# ProPrj_BLDC_complete_drive_controller_RE.net
KiCad netlist of a schematic drawn in EasyEDA Pro
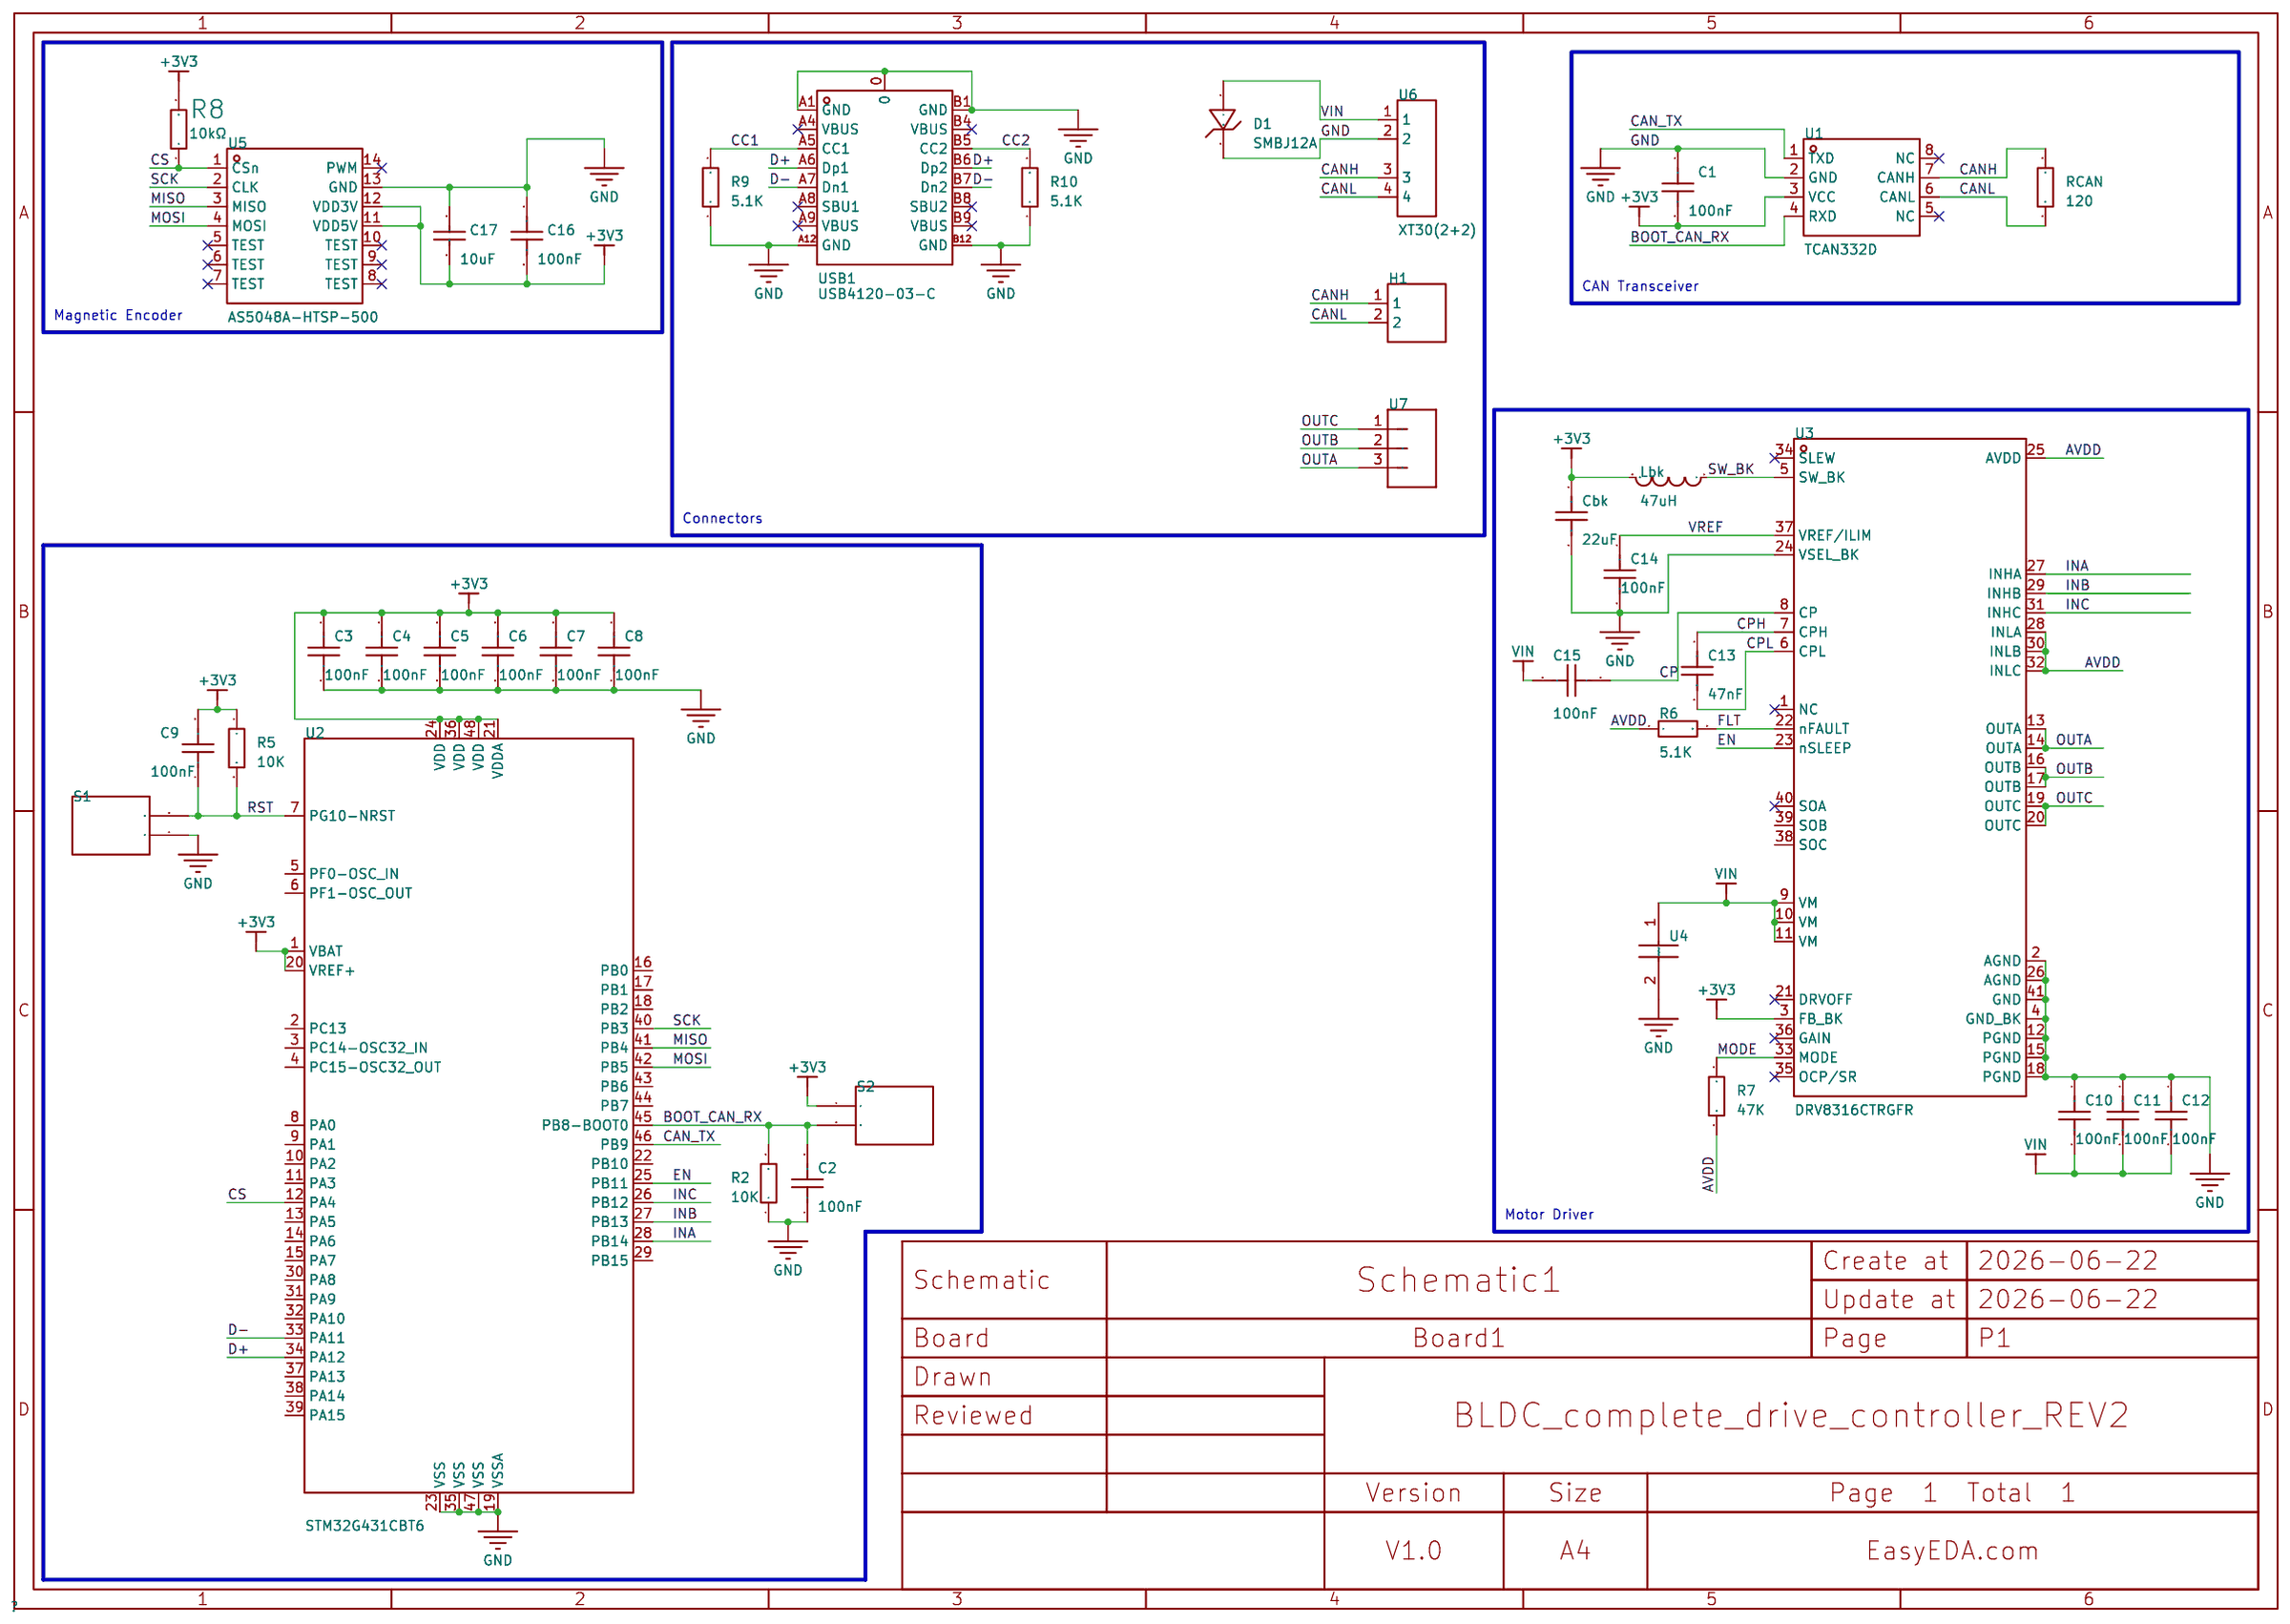
[diagram p0: schematic sheet]

(export (version "E")
  (design (tool "Eeschema 10.0.6"))
  (components
    (comp (ref "C1")
      (value "100nF")
      (footprint "easyedapro:C0603")
      (libsource (lib "easyedapro") (part "CAP"))
    )
    (comp (ref "C2")
      (value "100nF")
      (footprint "easyedapro:C0603")
      (libsource (lib "easyedapro") (part "CAP"))
    )
    (comp (ref "C3")
      (value "100nF")
      (footprint "easyedapro:C0603")
      (libsource (lib "easyedapro") (part "CAP"))
    )
    (comp (ref "C4")
      (value "100nF")
      (footprint "easyedapro:C0603")
      (libsource (lib "easyedapro") (part "CAP"))
    )
    (comp (ref "C5")
      (value "100nF")
      (footprint "easyedapro:C0603")
      (libsource (lib "easyedapro") (part "CAP"))
    )
    (comp (ref "C6")
      (value "100nF")
      (footprint "easyedapro:C0603")
      (libsource (lib "easyedapro") (part "CAP"))
    )
    (comp (ref "C7")
      (value "100nF")
      (footprint "easyedapro:C0603")
      (libsource (lib "easyedapro") (part "CAP"))
    )
    (comp (ref "C8")
      (value "100nF")
      (footprint "easyedapro:C0603")
      (libsource (lib "easyedapro") (part "CAP"))
    )
    (comp (ref "C9")
      (value "100nF")
      (footprint "easyedapro:C0603")
      (libsource (lib "easyedapro") (part "CAP"))
    )
    (comp (ref "C10")
      (value "100nF")
      (footprint "easyedapro:C0603")
      (libsource (lib "easyedapro") (part "CAP"))
    )
    (comp (ref "C11")
      (value "100nF")
      (footprint "easyedapro:C0603")
      (libsource (lib "easyedapro") (part "CAP"))
    )
    (comp (ref "C12")
      (value "100nF")
      (footprint "easyedapro:C0603")
      (libsource (lib "easyedapro") (part "CAP"))
    )
    (comp (ref "C13")
      (value "47nF")
      (footprint "easyedapro:C0603")
      (libsource (lib "easyedapro") (part "CAP"))
    )
    (comp (ref "C14")
      (value "100nF")
      (footprint "easyedapro:C0603")
      (libsource (lib "easyedapro") (part "CAP"))
    )
    (comp (ref "C15")
      (value "100nF")
      (footprint "easyedapro:C0603")
      (libsource (lib "easyedapro") (part "CAP"))
    )
    (comp (ref "C16")
      (value "100nF")
      (footprint "easyedapro:C0603")
      (description "Capacitance:100nF Tolerance:±10% Tolerance:±10% Voltage Rating:50V Temperature Coefficient:X7R")
      (fields
        (field (name "Manufacturer Part") "CC0603KRX7R9BB104")
        (field (name "Manufacturer") "YAGEO(国巨)")
      )
      (libsource (lib "easyedapro") (part "CC0603KRX7R9BB104"))
    )
    (comp (ref "C17")
      (value "10uF")
      (footprint "easyedapro:C0402")
      (description "Capacitance:10uF Tolerance:±20% Tolerance:±20% Voltage Rating:6.3V Temperature Coefficient:X5R")
      (fields
        (field (name "Manufacturer Part") "CL05A106MQ5NUNC")
        (field (name "Manufacturer") "SAMSUNG(三星)")
      )
      (libsource (lib "easyedapro") (part "CL05A106MQ5NUNC"))
    )
    (comp (ref "Cbk")
      (value "22uF")
      (footprint "easyedapro:C0603")
      (libsource (lib "easyedapro") (part "CAP"))
    )
    (comp (ref "D1")
      (value "SMBJ12A")
      (footprint "easyedapro:SMB_L4.6-W3.6-LS5.3-RD")
      (libsource (lib "easyedapro") (part "SMBJ12A-C127552"))
    )
    (comp (ref "H1")
      (value "~")
      (footprint "easyedapro:HDR-TH_2P-P2.54-V-M-1")
      (libsource (lib "easyedapro") (part "210S-1*2P L=11.6MMGold-plated black"))
    )
    (comp (ref "Lbk")
      (value "47uH")
      (footprint "easyedapro:L0805")
      (libsource (lib "easyedapro") (part "电感"))
    )
    (comp (ref "R2") (value "10K") (footprint "easyedapro:R0402") (libsource (lib "easyedapro") (part "Res")))
    (comp (ref "R5") (value "10K") (footprint "easyedapro:R0402") (libsource (lib "easyedapro") (part "Res")))
    (comp (ref "R6")
      (value "5.1K")
      (footprint "easyedapro:R0402")
      (libsource (lib "easyedapro") (part "Res"))
    )
    (comp (ref "R7") (value "47K") (footprint "easyedapro:R0402") (libsource (lib "easyedapro") (part "Res")))
    (comp (ref "R8")
      (value "10kΩ")
      (footprint "easyedapro:R0603")
      (fields
        (field (name "Manufacturer Part") "0603WAF1002T5E")
        (field (name "Manufacturer") "UNI-ROYAL(厚声)")
        (field (name "Tolerance") "±1%")
      )
      (libsource (lib "easyedapro") (part "0603WAF1002T5E"))
    )
    (comp (ref "R9")
      (value "5.1K")
      (footprint "easyedapro:R0402")
      (libsource (lib "easyedapro") (part "Res"))
    )
    (comp (ref "R10")
      (value "5.1K")
      (footprint "easyedapro:R0402")
      (libsource (lib "easyedapro") (part "Res"))
    )
    (comp (ref "RCAN")
      (value "120")
      (footprint "easyedapro:R0402")
      (libsource (lib "easyedapro") (part "Res"))
    )
    (comp (ref "S1")
      (value "~")
      (footprint "easyedapro:95C04A3GWRT")
      (libsource (lib "easyedapro") (part "95c04a3gwrt"))
    )
    (comp (ref "S2")
      (value "~")
      (footprint "easyedapro:95C04A3GWRT")
      (libsource (lib "easyedapro") (part "95c04a3gwrt"))
    )
    (comp (ref "U1")
      (value "TCAN332D")
      (footprint "easyedapro:SOIC-8_L4.9-W3.9-P1.27-LS6.0-BL")
      (fields (field (name "Manufacturer") "TI(德州仪器)"))
      (libsource (lib "easyedapro") (part "TCAN332D"))
    )
    (comp (ref "U2")
      (value "STM32G431CBT6")
      (footprint "easyedapro:LQFP-48_L7.0-W7.0-P0.50-LS9.0-BL")
      (fields (field (name "Manufacturer") "ST(意法半导体)"))
      (libsource (lib "easyedapro") (part "STM32G431CBT6"))
    )
    (comp (ref "U3")
      (value "DRV8316CTRGFR")
      (footprint "easyedapro:VQFN-40_L7.0-W5.0-P0.50-TL-EP5.7")
      (fields (field (name "Manufacturer") "TI(德州仪器)"))
      (libsource (lib "easyedapro") (part "DRV8316CTRGFR"))
    )
    (comp (ref "U4")
      (value "aha0608470m035r")
      (footprint "easyedapro:CAPAE660X850N")
      (libsource (lib "easyedapro") (part "aha0608470m035r"))
    )
    (comp (ref "U5")
      (value "AS5048A-HTSP-500")
      (footprint "easyedapro:TSSOP-14_L5.0-W4.4-P0.65-LS6.4-BL")
      (fields (field (name "Manufacturer") "ams(艾迈斯半导体)"))
      (libsource (lib "easyedapro") (part "AS5048A-HTSP-500"))
    )
    (comp (ref "U6")
      (value "XT30(2+2)")
      (footprint "easyedapro:CONN-TH_XT30-2-2")
      (libsource (lib "easyedapro") (part "XT30(2+2)"))
    )
    (comp (ref "U7")
      (value "~")
      (footprint "easyedapro:SCREWTERMINAL-3.5MM-3")
      (libsource (lib "easyedapro") (part "CONN_03_SCREW"))
    )
    (comp (ref "USB1")
      (value "USB4120-03-C")
      (footprint "easyedapro:TYPE-C-SMD_USB4120-03-C")
      (fields (field (name "Manufacturer") "GCT"))
      (libsource (lib "easyedapro") (part "USB4120-03-C"))
    )
  )
  (nets
    (net (code "1") (name "+3V3") (class "Default")
      (node (ref "C1") (pin "2") (pinfunction "2_2") (pintype "input"))
      (node (ref "C16") (pin "2") (pinfunction "2_2") (pintype "unspecified"))
      (node (ref "C17") (pin "1") (pinfunction "1_1") (pintype "input"))
      (node (ref "C3") (pin "2") (pinfunction "2_2") (pintype "input"))
      (node (ref "C4") (pin "2") (pinfunction "2_2") (pintype "input"))
      (node (ref "C5") (pin "2") (pinfunction "2_2") (pintype "input"))
      (node (ref "C6") (pin "2") (pinfunction "2_2") (pintype "input"))
      (node (ref "C7") (pin "2") (pinfunction "2_2") (pintype "input"))
      (node (ref "C8") (pin "2") (pinfunction "2_2") (pintype "input"))
      (node (ref "C9") (pin "2") (pinfunction "2_2") (pintype "input"))
      (node (ref "Cbk") (pin "1") (pinfunction "1_1") (pintype "input"))
      (node (ref "Lbk") (pin "2") (pinfunction "2_2") (pintype "input"))
      (node (ref "R5") (pin "1") (pinfunction "1_1") (pintype "input"))
      (node (ref "R8") (pin "2") (pinfunction "2_2") (pintype "input"))
      (node (ref "S2") (pin "1") (pinfunction "1_1") (pintype "unspecified"))
      (node (ref "U1") (pin "3") (pinfunction "VCC_3") (pintype "input"))
      (node (ref "U2") (pin "1") (pinfunction "VBAT_1") (pintype "unspecified"))
      (node (ref "U2") (pin "20") (pinfunction "VREF+_20") (pintype "unspecified"))
      (node (ref "U2") (pin "21") (pinfunction "VDDA_21") (pintype "unspecified"))
      (node (ref "U2") (pin "24") (pinfunction "VDD_24") (pintype "unspecified"))
      (node (ref "U2") (pin "36") (pinfunction "VDD_36") (pintype "unspecified"))
      (node (ref "U2") (pin "48") (pinfunction "VDD_48") (pintype "unspecified"))
      (node (ref "U3") (pin "3") (pinfunction "FB_BK_3") (pintype "unspecified"))
      (node (ref "U5") (pin "11") (pinfunction "VDD5V_11") (pintype "unspecified"))
      (node (ref "U5") (pin "12") (pinfunction "VDD3V_12") (pintype "unspecified"))
    )
    (net (code "2") (name "/AVDD") (class "Default")
      (node (ref "R6") (pin "1") (pinfunction "1_1") (pintype "input"))
      (node (ref "R7") (pin "2") (pinfunction "2_2") (pintype "input"))
      (node (ref "U3") (pin "25") (pinfunction "AVDD_25") (pintype "unspecified"))
      (node (ref "U3") (pin "28") (pinfunction "INLA_28") (pintype "unspecified"))
      (node (ref "U3") (pin "30") (pinfunction "INLB_30") (pintype "unspecified"))
      (node (ref "U3") (pin "32") (pinfunction "INLC_32") (pintype "unspecified"))
    )
    (net (code "3") (name "/BOOT_CAN_RX") (class "Default")
      (node (ref "C2") (pin "2") (pinfunction "2_2") (pintype "input"))
      (node (ref "R2") (pin "2") (pinfunction "2_2") (pintype "input"))
      (node (ref "S2") (pin "2") (pinfunction "2_2") (pintype "unspecified"))
      (node (ref "U1") (pin "4") (pinfunction "RXD_4") (pintype "input"))
      (node (ref "U2") (pin "45") (pinfunction "PB8-BOOT0_45") (pintype "unspecified"))
    )
    (net (code "4") (name "/CANH") (class "Default")
      (node (ref "H1") (pin "1") (pinfunction "1_1") (pintype "unspecified"))
      (node (ref "RCAN") (pin "2") (pinfunction "2_2") (pintype "input"))
      (node (ref "U1") (pin "7") (pinfunction "CANH_7") (pintype "input"))
      (node (ref "U6") (pin "3") (pinfunction "3_3") (pintype "unspecified"))
    )
    (net (code "5") (name "/CANL") (class "Default")
      (node (ref "H1") (pin "2") (pinfunction "2_2") (pintype "unspecified"))
      (node (ref "RCAN") (pin "1") (pinfunction "1_1") (pintype "input"))
      (node (ref "U1") (pin "6") (pinfunction "CANL_6") (pintype "input"))
      (node (ref "U6") (pin "4") (pinfunction "4_4") (pintype "unspecified"))
    )
    (net (code "6") (name "/CAN_TX") (class "Default")
      (node (ref "U1") (pin "1") (pinfunction "TXD_1") (pintype "input"))
      (node (ref "U2") (pin "46") (pinfunction "PB9_46") (pintype "unspecified"))
    )
    (net (code "7") (name "/CC1") (class "Default")
      (node (ref "R9") (pin "2") (pinfunction "2_2") (pintype "input"))
      (node (ref "USB1") (pin "A5") (pinfunction "CC1_A5") (pintype "unspecified"))
    )
    (net (code "8") (name "/CC2") (class "Default")
      (node (ref "R10") (pin "2") (pinfunction "2_2") (pintype "input"))
      (node (ref "USB1") (pin "B5") (pinfunction "CC2_B5") (pintype "unspecified"))
    )
    (net (code "9") (name "/CP") (class "Default")
      (node (ref "C15") (pin "1") (pinfunction "1_1") (pintype "input"))
      (node (ref "U3") (pin "8") (pinfunction "CP_8") (pintype "unspecified"))
    )
    (net (code "10") (name "/CPH") (class "Default")
      (node (ref "C13") (pin "1") (pinfunction "1_1") (pintype "input"))
      (node (ref "U3") (pin "7") (pinfunction "CPH_7") (pintype "unspecified"))
    )
    (net (code "11") (name "/CPL") (class "Default")
      (node (ref "C13") (pin "2") (pinfunction "2_2") (pintype "input"))
      (node (ref "U3") (pin "6") (pinfunction "CPL_6") (pintype "unspecified"))
    )
    (net (code "12") (name "/CS") (class "Default")
      (node (ref "R8") (pin "1") (pinfunction "1_1") (pintype "input"))
      (node (ref "U2") (pin "12") (pinfunction "PA4_12") (pintype "unspecified"))
      (node (ref "U5") (pin "1") (pinfunction "CSn_1") (pintype "unspecified"))
    )
    (net (code "13") (name "/D+") (class "Default")
      (node (ref "U2") (pin "34") (pinfunction "PA12_34") (pintype "unspecified"))
      (node (ref "USB1") (pin "A6") (pinfunction "Dp1_A6") (pintype "unspecified"))
      (node (ref "USB1") (pin "B6") (pinfunction "Dp2_B6") (pintype "unspecified"))
    )
    (net (code "14") (name "/D-") (class "Default")
      (node (ref "U2") (pin "33") (pinfunction "PA11_33") (pintype "unspecified"))
      (node (ref "USB1") (pin "A7") (pinfunction "Dn1_A7") (pintype "unspecified"))
      (node (ref "USB1") (pin "B7") (pinfunction "Dn2_B7") (pintype "unspecified"))
    )
    (net (code "15") (name "/EN") (class "Default")
      (node (ref "U2") (pin "25") (pinfunction "PB11_25") (pintype "unspecified"))
      (node (ref "U3") (pin "23") (pinfunction "nSLEEP_23") (pintype "unspecified"))
    )
    (net (code "16") (name "/FLT") (class "Default")
      (node (ref "R6") (pin "2") (pinfunction "2_2") (pintype "input"))
      (node (ref "U3") (pin "22") (pinfunction "nFAULT_22") (pintype "unspecified"))
    )
    (net (code "17") (name "/INA") (class "Default")
      (node (ref "U2") (pin "28") (pinfunction "PB14_28") (pintype "unspecified"))
      (node (ref "U3") (pin "27") (pinfunction "INHA_27") (pintype "unspecified"))
    )
    (net (code "18") (name "/INB") (class "Default")
      (node (ref "U2") (pin "27") (pinfunction "PB13_27") (pintype "unspecified"))
      (node (ref "U3") (pin "29") (pinfunction "INHB_29") (pintype "unspecified"))
    )
    (net (code "19") (name "/INC") (class "Default")
      (node (ref "U2") (pin "26") (pinfunction "PB12_26") (pintype "unspecified"))
      (node (ref "U3") (pin "31") (pinfunction "INHC_31") (pintype "unspecified"))
    )
    (net (code "20") (name "/MISO") (class "Default")
      (node (ref "U2") (pin "41") (pinfunction "PB4_41") (pintype "unspecified"))
      (node (ref "U5") (pin "3") (pinfunction "MISO_3") (pintype "unspecified"))
    )
    (net (code "21") (name "/MODE") (class "Default")
      (node (ref "R7") (pin "1") (pinfunction "1_1") (pintype "input"))
      (node (ref "U3") (pin "33") (pinfunction "MODE_33") (pintype "unspecified"))
    )
    (net (code "22") (name "/MOSI") (class "Default")
      (node (ref "U2") (pin "42") (pinfunction "PB5_42") (pintype "unspecified"))
      (node (ref "U5") (pin "4") (pinfunction "MOSI_4") (pintype "unspecified"))
    )
    (net (code "23") (name "/OUTA") (class "Default")
      (node (ref "U3") (pin "13") (pinfunction "OUTA_13") (pintype "unspecified"))
      (node (ref "U3") (pin "14") (pinfunction "OUTA_14") (pintype "unspecified"))
      (node (ref "U7") (pin "3") (pinfunction "3_3") (pintype "unspecified"))
    )
    (net (code "24") (name "/OUTB") (class "Default")
      (node (ref "U3") (pin "16") (pinfunction "OUTB_16") (pintype "unspecified"))
      (node (ref "U3") (pin "17") (pinfunction "OUTB_17") (pintype "unspecified"))
      (node (ref "U7") (pin "2") (pinfunction "2_2") (pintype "unspecified"))
    )
    (net (code "25") (name "/OUTC") (class "Default")
      (node (ref "U3") (pin "19") (pinfunction "OUTC_19") (pintype "unspecified"))
      (node (ref "U3") (pin "20") (pinfunction "OUTC_20") (pintype "unspecified"))
      (node (ref "U7") (pin "1") (pinfunction "1_1") (pintype "unspecified"))
    )
    (net (code "26") (name "/RST") (class "Default")
      (node (ref "C9") (pin "1") (pinfunction "1_1") (pintype "input"))
      (node (ref "R5") (pin "2") (pinfunction "2_2") (pintype "input"))
      (node (ref "S1") (pin "2") (pinfunction "2_2") (pintype "unspecified"))
      (node (ref "U2") (pin "7") (pinfunction "PG10-NRST_7") (pintype "unspecified"))
    )
    (net (code "27") (name "/SCK") (class "Default")
      (node (ref "U2") (pin "40") (pinfunction "PB3_40") (pintype "unspecified"))
      (node (ref "U5") (pin "2") (pinfunction "CLK_2") (pintype "unspecified"))
    )
    (net (code "28") (name "/SW_BK") (class "Default")
      (node (ref "Lbk") (pin "1") (pinfunction "1_1") (pintype "input"))
      (node (ref "U3") (pin "5") (pinfunction "SW_BK_5") (pintype "unspecified"))
    )
    (net (code "29") (name "/VREF") (class "Default")
      (node (ref "C14") (pin "1") (pinfunction "1_1") (pintype "input"))
      (node (ref "U3") (pin "37") (pinfunction "VREF/ILIM_37") (pintype "unspecified"))
    )
    (net (code "30") (name "GND") (class "Default")
      (node (ref "C1") (pin "1") (pinfunction "1_1") (pintype "input"))
      (node (ref "C10") (pin "1") (pinfunction "1_1") (pintype "input"))
      (node (ref "C11") (pin "1") (pinfunction "1_1") (pintype "input"))
      (node (ref "C12") (pin "1") (pinfunction "1_1") (pintype "input"))
      (node (ref "C14") (pin "2") (pinfunction "2_2") (pintype "input"))
      (node (ref "C16") (pin "1") (pinfunction "1_1") (pintype "unspecified"))
      (node (ref "C17") (pin "2") (pinfunction "2_2") (pintype "input"))
      (node (ref "C2") (pin "1") (pinfunction "1_1") (pintype "input"))
      (node (ref "C3") (pin "1") (pinfunction "1_1") (pintype "input"))
      (node (ref "C4") (pin "1") (pinfunction "1_1") (pintype "input"))
      (node (ref "C5") (pin "1") (pinfunction "1_1") (pintype "input"))
      (node (ref "C6") (pin "1") (pinfunction "1_1") (pintype "input"))
      (node (ref "C7") (pin "1") (pinfunction "1_1") (pintype "input"))
      (node (ref "C8") (pin "1") (pinfunction "1_1") (pintype "input"))
      (node (ref "Cbk") (pin "2") (pinfunction "2_2") (pintype "input"))
      (node (ref "D1") (pin "1") (pinfunction "C_1") (pintype "unspecified"))
      (node (ref "R10") (pin "1") (pinfunction "1_1") (pintype "input"))
      (node (ref "R2") (pin "1") (pinfunction "1_1") (pintype "input"))
      (node (ref "R9") (pin "1") (pinfunction "1_1") (pintype "input"))
      (node (ref "S1") (pin "1") (pinfunction "1_1") (pintype "unspecified"))
      (node (ref "U1") (pin "2") (pinfunction "GND_2") (pintype "input"))
      (node (ref "U2") (pin "19") (pinfunction "VSSA_19") (pintype "unspecified"))
      (node (ref "U2") (pin "23") (pinfunction "VSS_23") (pintype "unspecified"))
      (node (ref "U2") (pin "35") (pinfunction "VSS_35") (pintype "unspecified"))
      (node (ref "U2") (pin "47") (pinfunction "VSS_47") (pintype "unspecified"))
      (node (ref "U3") (pin "12") (pinfunction "PGND_12") (pintype "unspecified"))
      (node (ref "U3") (pin "15") (pinfunction "PGND_15") (pintype "unspecified"))
      (node (ref "U3") (pin "18") (pinfunction "PGND_18") (pintype "unspecified"))
      (node (ref "U3") (pin "2") (pinfunction "AGND_2") (pintype "unspecified"))
      (node (ref "U3") (pin "24") (pinfunction "VSEL_BK_24") (pintype "unspecified"))
      (node (ref "U3") (pin "26") (pinfunction "AGND_26") (pintype "unspecified"))
      (node (ref "U3") (pin "4") (pinfunction "GND_BK_4") (pintype "unspecified"))
      (node (ref "U3") (pin "41") (pinfunction "GND_41") (pintype "unspecified"))
      (node (ref "U4") (pin "2") (pinfunction "~_2") (pintype "unspecified"))
      (node (ref "U5") (pin "13") (pinfunction "GND_13") (pintype "unspecified"))
      (node (ref "U6") (pin "2") (pinfunction "2_2") (pintype "unspecified"))
      (node (ref "USB1") (pin "0") (pinfunction "0_0") (pintype "unspecified"))
      (node (ref "USB1") (pin "A1") (pinfunction "GND_A1") (pintype "unspecified"))
      (node (ref "USB1") (pin "A12") (pinfunction "GND_A12") (pintype "unspecified"))
      (node (ref "USB1") (pin "B1") (pinfunction "GND_B1") (pintype "unspecified"))
      (node (ref "USB1") (pin "B12") (pinfunction "GND_B12") (pintype "unspecified"))
    )
    (net (code "31") (name "VIN") (class "Default")
      (node (ref "C10") (pin "2") (pinfunction "2_2") (pintype "input"))
      (node (ref "C11") (pin "2") (pinfunction "2_2") (pintype "input"))
      (node (ref "C12") (pin "2") (pinfunction "2_2") (pintype "input"))
      (node (ref "C15") (pin "2") (pinfunction "2_2") (pintype "input"))
      (node (ref "D1") (pin "2") (pinfunction "A_2") (pintype "unspecified"))
      (node (ref "U3") (pin "10") (pinfunction "VM_10") (pintype "unspecified"))
      (node (ref "U3") (pin "11") (pinfunction "VM_11") (pintype "unspecified"))
      (node (ref "U3") (pin "9") (pinfunction "VM_9") (pintype "unspecified"))
      (node (ref "U4") (pin "1") (pinfunction "~_1") (pintype "unspecified"))
      (node (ref "U6") (pin "1") (pinfunction "1_1") (pintype "unspecified"))
    )
    (net (code "32") (name "unconnected-(U1-NC-Pad5)") (class "Default")
      (node (ref "U1") (pin "5") (pinfunction "NC_5") (pintype "input+no_connect"))
    )
    (net (code "33") (name "unconnected-(U1-NC-Pad8)") (class "Default")
      (node (ref "U1") (pin "8") (pinfunction "NC_8") (pintype "input+no_connect"))
    )
    (net (code "34") (name "unconnected-(U2-PA0-Pad8)") (class "Default")
      (node (ref "U2") (pin "8") (pinfunction "PA0_8") (pintype "unspecified"))
    )
    (net (code "35") (name "unconnected-(U2-PA1-Pad9)") (class "Default")
      (node (ref "U2") (pin "9") (pinfunction "PA1_9") (pintype "unspecified"))
    )
    (net (code "36") (name "unconnected-(U2-PA2-Pad10)") (class "Default")
      (node (ref "U2") (pin "10") (pinfunction "PA2_10") (pintype "unspecified"))
    )
    (net (code "37") (name "unconnected-(U2-PA3-Pad11)") (class "Default")
      (node (ref "U2") (pin "11") (pinfunction "PA3_11") (pintype "unspecified"))
    )
    (net (code "38") (name "unconnected-(U2-PA5-Pad13)") (class "Default")
      (node (ref "U2") (pin "13") (pinfunction "PA5_13") (pintype "unspecified"))
    )
    (net (code "39") (name "unconnected-(U2-PA6-Pad14)") (class "Default")
      (node (ref "U2") (pin "14") (pinfunction "PA6_14") (pintype "unspecified"))
    )
    (net (code "40") (name "unconnected-(U2-PA7-Pad15)") (class "Default")
      (node (ref "U2") (pin "15") (pinfunction "PA7_15") (pintype "unspecified"))
    )
    (net (code "41") (name "unconnected-(U2-PA8-Pad30)") (class "Default")
      (node (ref "U2") (pin "30") (pinfunction "PA8_30") (pintype "unspecified"))
    )
    (net (code "42") (name "unconnected-(U2-PA9-Pad31)") (class "Default")
      (node (ref "U2") (pin "31") (pinfunction "PA9_31") (pintype "unspecified"))
    )
    (net (code "43") (name "unconnected-(U2-PA10-Pad32)") (class "Default")
      (node (ref "U2") (pin "32") (pinfunction "PA10_32") (pintype "unspecified"))
    )
    (net (code "44") (name "unconnected-(U2-PA13-Pad37)") (class "Default")
      (node (ref "U2") (pin "37") (pinfunction "PA13_37") (pintype "unspecified"))
    )
    (net (code "45") (name "unconnected-(U2-PA14-Pad38)") (class "Default")
      (node (ref "U2") (pin "38") (pinfunction "PA14_38") (pintype "unspecified"))
    )
    (net (code "46") (name "unconnected-(U2-PA15-Pad39)") (class "Default")
      (node (ref "U2") (pin "39") (pinfunction "PA15_39") (pintype "unspecified"))
    )
    (net (code "47") (name "unconnected-(U2-PB0-Pad16)") (class "Default")
      (node (ref "U2") (pin "16") (pinfunction "PB0_16") (pintype "unspecified"))
    )
    (net (code "48") (name "unconnected-(U2-PB1-Pad17)") (class "Default")
      (node (ref "U2") (pin "17") (pinfunction "PB1_17") (pintype "unspecified"))
    )
    (net (code "49") (name "unconnected-(U2-PB2-Pad18)") (class "Default")
      (node (ref "U2") (pin "18") (pinfunction "PB2_18") (pintype "unspecified"))
    )
    (net (code "50") (name "unconnected-(U2-PB6-Pad43)") (class "Default")
      (node (ref "U2") (pin "43") (pinfunction "PB6_43") (pintype "unspecified"))
    )
    (net (code "51") (name "unconnected-(U2-PB7-Pad44)") (class "Default")
      (node (ref "U2") (pin "44") (pinfunction "PB7_44") (pintype "unspecified"))
    )
    (net (code "52") (name "unconnected-(U2-PB10-Pad22)") (class "Default")
      (node (ref "U2") (pin "22") (pinfunction "PB10_22") (pintype "unspecified"))
    )
    (net (code "53") (name "unconnected-(U2-PB15-Pad29)") (class "Default")
      (node (ref "U2") (pin "29") (pinfunction "PB15_29") (pintype "unspecified"))
    )
    (net (code "54") (name "unconnected-(U2-PC13-Pad2)") (class "Default")
      (node (ref "U2") (pin "2") (pinfunction "PC13_2") (pintype "unspecified"))
    )
    (net (code "55") (name "unconnected-(U2-PC14-OSC32_IN-Pad3)") (class "Default")
      (node (ref "U2") (pin "3") (pinfunction "PC14-OSC32_IN_3") (pintype "unspecified"))
    )
    (net (code "56") (name "unconnected-(U2-PC15-OSC32_OUT-Pad4)") (class "Default")
      (node (ref "U2") (pin "4") (pinfunction "PC15-OSC32_OUT_4") (pintype "unspecified"))
    )
    (net (code "57") (name "unconnected-(U2-PF0-OSC_IN-Pad5)") (class "Default")
      (node (ref "U2") (pin "5") (pinfunction "PF0-OSC_IN_5") (pintype "unspecified"))
    )
    (net (code "58") (name "unconnected-(U2-PF1-OSC_OUT-Pad6)") (class "Default")
      (node (ref "U2") (pin "6") (pinfunction "PF1-OSC_OUT_6") (pintype "unspecified"))
    )
    (net (code "59") (name "unconnected-(U3-DRVOFF-Pad21)") (class "Default")
      (node (ref "U3") (pin "21") (pinfunction "DRVOFF_21") (pintype "unspecified+no_connect"))
    )
    (net (code "60") (name "unconnected-(U3-GAIN-Pad36)") (class "Default")
      (node (ref "U3") (pin "36") (pinfunction "GAIN_36") (pintype "unspecified+no_connect"))
    )
    (net (code "61") (name "unconnected-(U3-NC-Pad1)") (class "Default")
      (node (ref "U3") (pin "1") (pinfunction "NC_1") (pintype "unspecified+no_connect"))
    )
    (net (code "62") (name "unconnected-(U3-OCP{slash}SR-Pad35)") (class "Default")
      (node (ref "U3") (pin "35") (pinfunction "OCP/SR_35") (pintype "unspecified+no_connect"))
    )
    (net (code "63") (name "unconnected-(U3-SLEW-Pad34)") (class "Default")
      (node (ref "U3") (pin "34") (pinfunction "SLEW_34") (pintype "unspecified+no_connect"))
    )
    (net (code "64") (name "unconnected-(U3-SOA-Pad40)") (class "Default")
      (node (ref "U3") (pin "40") (pinfunction "SOA_40") (pintype "unspecified+no_connect"))
    )
    (net (code "65") (name "unconnected-(U3-SOB-Pad39)") (class "Default")
      (node (ref "U3") (pin "39") (pinfunction "SOB_39") (pintype "unspecified"))
    )
    (net (code "66") (name "unconnected-(U3-SOC-Pad38)") (class "Default")
      (node (ref "U3") (pin "38") (pinfunction "SOC_38") (pintype "unspecified"))
    )
    (net (code "67") (name "unconnected-(U5-PWM-Pad14)") (class "Default")
      (node (ref "U5") (pin "14") (pinfunction "PWM_14") (pintype "unspecified+no_connect"))
    )
    (net (code "68") (name "unconnected-(U5-TEST-Pad5)") (class "Default")
      (node (ref "U5") (pin "5") (pinfunction "TEST_5") (pintype "unspecified+no_connect"))
    )
    (net (code "69") (name "unconnected-(U5-TEST-Pad6)") (class "Default")
      (node (ref "U5") (pin "6") (pinfunction "TEST_6") (pintype "unspecified+no_connect"))
    )
    (net (code "70") (name "unconnected-(U5-TEST-Pad7)") (class "Default")
      (node (ref "U5") (pin "7") (pinfunction "TEST_7") (pintype "unspecified+no_connect"))
    )
    (net (code "71") (name "unconnected-(U5-TEST-Pad8)") (class "Default")
      (node (ref "U5") (pin "8") (pinfunction "TEST_8") (pintype "unspecified+no_connect"))
    )
    (net (code "72") (name "unconnected-(U5-TEST-Pad9)") (class "Default")
      (node (ref "U5") (pin "9") (pinfunction "TEST_9") (pintype "unspecified+no_connect"))
    )
    (net (code "73") (name "unconnected-(U5-TEST-Pad10)") (class "Default")
      (node (ref "U5") (pin "10") (pinfunction "TEST_10") (pintype "unspecified+no_connect"))
    )
    (net (code "74") (name "unconnected-(USB1-SBU1-PadA8)") (class "Default")
      (node (ref "USB1") (pin "A8") (pinfunction "SBU1_A8") (pintype "unspecified+no_connect"))
    )
    (net (code "75") (name "unconnected-(USB1-SBU2-PadB8)") (class "Default")
      (node (ref "USB1") (pin "B8") (pinfunction "SBU2_B8") (pintype "unspecified+no_connect"))
    )
    (net (code "76") (name "unconnected-(USB1-VBUS-PadA4)") (class "Default")
      (node (ref "USB1") (pin "A4") (pinfunction "VBUS_A4") (pintype "unspecified+no_connect"))
    )
    (net (code "77") (name "unconnected-(USB1-VBUS-PadA9)") (class "Default")
      (node (ref "USB1") (pin "A9") (pinfunction "VBUS_A9") (pintype "unspecified+no_connect"))
    )
    (net (code "78") (name "unconnected-(USB1-VBUS-PadB4)") (class "Default")
      (node (ref "USB1") (pin "B4") (pinfunction "VBUS_B4") (pintype "unspecified+no_connect"))
    )
    (net (code "79") (name "unconnected-(USB1-VBUS-PadB9)") (class "Default")
      (node (ref "USB1") (pin "B9") (pinfunction "VBUS_B9") (pintype "unspecified+no_connect"))
    )
  )
)
